# LCD.net
KiCad netlist of a schematic drawn in Altium Designer
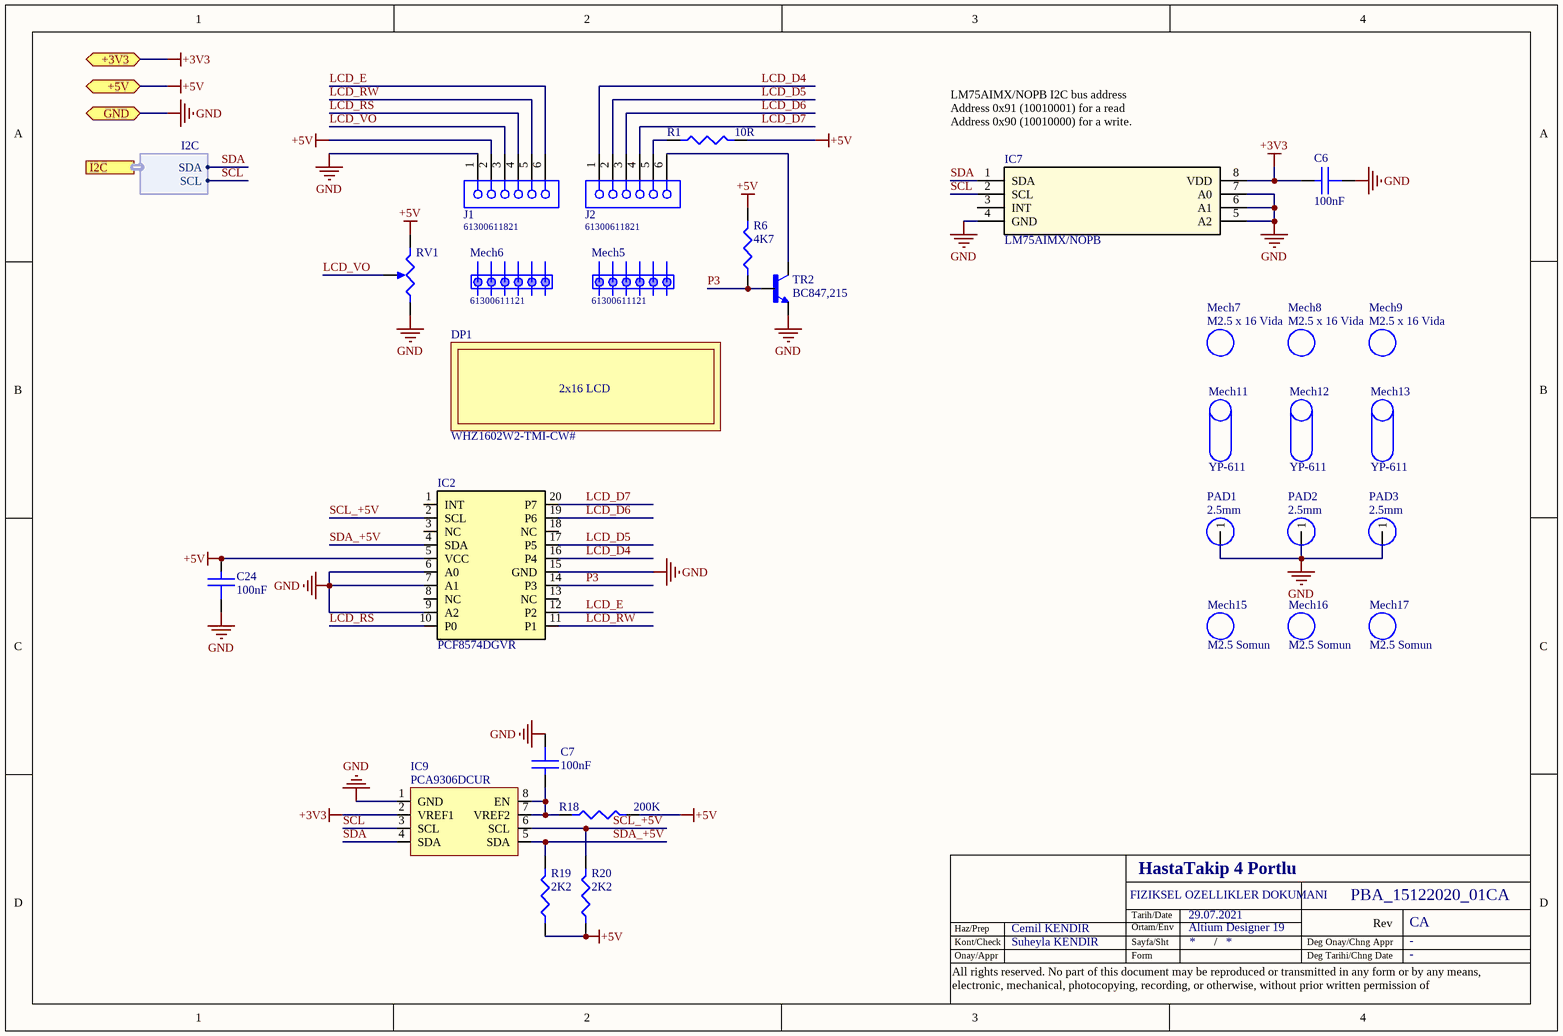
[diagram p0: LCD.SchDoc]

(export (version "E")
  (design (tool "Eeschema 10.0.6"))
  (components
    (comp (ref "C6")
      (value "100nF")
      (footprint "C0603")
      (description "100nF, 25V, X7R, 10%, 0603")
      (fields
        (field (name "MANUFACTURER") "Yageo")
        (field (name "MANUFACTURER PART NUMBER") "CC0603KRX7R8BB104")
      )
      (libsource (lib "McmLibrary") (part "CC0603KRX7R8BB104"))
    )
    (comp (ref "C7")
      (value "100nF")
      (footprint "C0603")
      (description "100nF, 25V, X7R, 10%, 0603")
      (fields
        (field (name "MANUFACTURER") "Yageo")
        (field (name "MANUFACTURER PART NUMBER") "CC0603KRX7R8BB104")
      )
      (libsource (lib "McmLibrary") (part "CC0603KRX7R8BB104"))
    )
    (comp (ref "C24")
      (value "100nF")
      (footprint "C0603")
      (description "100nF, 25V, X7R, 10%, 0603")
      (fields
        (field (name "MANUFACTURER") "Yageo")
        (field (name "MANUFACTURER PART NUMBER") "CC0603KRX7R8BB104")
      )
      (libsource (lib "McmLibrary") (part "CC0603KRX7R8BB104"))
    )
    (comp (ref "DP1")
      (value "WHZ1602W2-TMI-CW#")
      (footprint "WHZ1602W2-TMI-CW#")
      (description "LCD MOD 16*2 80X36X10MM LEDB.LIGHT WHITE")
      (fields (field (name "MANUFACTURER") "Winstar"))
      (libsource (lib "McmLibrary") (part "WHZ1602W2-TMI-CW#"))
    )
    (comp (ref "IC2")
      (value "PCF8574DGVR")
      (footprint "DGV20")
      (description "8-bit 2.5- to 5.5-V I2C/SMBus I/O expander with interrupt 20-TVSOP -40 to 85")
      (fields (field (name "MANUFACTURER") "Texas Instruments"))
      (libsource (lib "McmLibrary") (part "PCF8574DGVR"))
    )
    (comp (ref "IC7")
      (value "LM75AIMX/NOPB")
      (footprint "SO08")
      (description "SENSOR DIGITAL -55C-125C 8SOIC")
      (fields (field (name "MANUFACTURER") "TI National Semiconductor"))
      (libsource (lib "Sensors") (part "LM75AIMX/NOPB"))
    )
    (comp (ref "IC9")
      (value "PCA9306DCUR")
      (footprint "SOP50P310X90-8N")
      (description "TEXAS INSTRUMENTS - PCA9306DCUR - 2 BIT VOLTAGE LEVEL TRANSLATOR VSSOP8")
      (fields (field (name "MANUFACTURER") "Texas Instruments"))
      (libsource (lib "McmLibrary") (part "PCA9306DCUR"))
    )
    (comp (ref "J1")
      (value "61300611821")
      (footprint "61300611821")
      (description "WR-PHD Socket Header, THT, pitch 2.54mm, Single Row, Vertical, 6pin")
      (fields (field (name "PUBLISHER") "Wurth Elektronik"))
      (libsource (lib "McmLibrary") (part "61300611821"))
    )
    (comp (ref "J2")
      (value "61300611821")
      (footprint "61300611821")
      (description "WR-PHD Socket Header, THT, pitch 2.54mm, Single Row, Vertical, 6pin")
      (fields (field (name "PUBLISHER") "Wurth Elektronik"))
      (libsource (lib "McmLibrary") (part "61300611821"))
    )
    (comp (ref "Mech5")
      (value "61300611121")
      (footprint "61300611121")
      (description "WR-PHD Pin Header, THT, pitch 2.54mm, Single Row, Vertical, 6pin")
      (fields (field (name "PUBLISHER") "Wurth Elektronik"))
      (libsource (lib "McmLibrary") (part "61300611121"))
    )
    (comp (ref "Mech6")
      (value "61300611121")
      (footprint "61300611121")
      (description "WR-PHD Pin Header, THT, pitch 2.54mm, Single Row, Vertical, 6pin")
      (fields (field (name "PUBLISHER") "Wurth Elektronik"))
      (libsource (lib "McmLibrary") (part "61300611121"))
    )
    (comp (ref "Mech7")
      (value "M2.5 x 16 Vida")
      (footprint "M2.5 x 16")
      (description "M2.5 x 16 YSB Vida")
      (libsource (lib "McmLibrary") (part "M2.5 x 16 Vida"))
    )
    (comp (ref "Mech8")
      (value "M2.5 x 16 Vida")
      (footprint "M2.5 x 16")
      (description "M2.5 x 16 YSB Vida")
      (libsource (lib "McmLibrary") (part "M2.5 x 16 Vida"))
    )
    (comp (ref "Mech9")
      (value "M2.5 x 16 Vida")
      (footprint "M2.5 x 16")
      (description "M2.5 x 16 YSB Vida")
      (libsource (lib "McmLibrary") (part "M2.5 x 16 Vida"))
    )
    (comp (ref "Mech11")
      (value "YP-611")
      (footprint "YP-611 - 11 mm")
      (description "Distance 2.5mmx11mm")
      (libsource (lib "McmLibrary") (part "YP-611"))
    )
    (comp (ref "Mech12")
      (value "YP-611")
      (footprint "YP-611 - 11 mm")
      (description "Distance 2.5mmx11mm")
      (libsource (lib "McmLibrary") (part "YP-611"))
    )
    (comp (ref "Mech13")
      (value "YP-611")
      (footprint "YP-611 - 11 mm")
      (description "Distance 2.5mmx11mm")
      (libsource (lib "McmLibrary") (part "YP-611"))
    )
    (comp (ref "Mech15")
      (value "M2.5 Somun")
      (footprint "M2.5")
      (libsource (lib "McmLibrary") (part "M2.5 Somun"))
    )
    (comp (ref "Mech16")
      (value "M2.5 Somun")
      (footprint "M2.5")
      (libsource (lib "McmLibrary") (part "M2.5 Somun"))
    )
    (comp (ref "Mech17")
      (value "M2.5 Somun")
      (footprint "M2.5")
      (libsource (lib "McmLibrary") (part "M2.5 Somun"))
    )
    (comp (ref "PAD1")
      (value "2.5mm")
      (footprint "2.5mm x 5mm")
      (description "5mm x 2.5mm Pad")
      (libsource (lib "McmLibrary") (part "2.5mm x 5mm PAD"))
    )
    (comp (ref "PAD2")
      (value "2.5mm")
      (footprint "2.5mm x 5mm")
      (description "5mm x 2.5mm Pad")
      (libsource (lib "McmLibrary") (part "2.5mm x 5mm PAD"))
    )
    (comp (ref "PAD3")
      (value "2.5mm")
      (footprint "2.5mm x 5mm")
      (description "5mm x 2.5mm Pad")
      (libsource (lib "McmLibrary") (part "2.5mm x 5mm PAD"))
    )
    (comp (ref "R1")
      (value "10R")
      (footprint "R0603")
      (description "10R ,%1 ,1/10 W ,0603")
      (fields
        (field (name "MANUFACTURER") "Yageo")
        (field (name "MANUFACTURER PART NUMBER") "RC0603FR-0710RL")
      )
      (libsource (lib "McmLibrary") (part "RC0603FR-0710RL"))
    )
    (comp (ref "R6")
      (value "4K7")
      (footprint "R0603")
      (description "4K7 ,%1 ,1/10 W ,0603")
      (fields
        (field (name "MANUFACTURER") "Yageo")
        (field (name "MANUFACTURER PART NUMBER") "RC0603FR-074K7L")
      )
      (libsource (lib "McmLibrary") (part "RC0603FR-074K7L"))
    )
    (comp (ref "R18")
      (value "200K")
      (footprint "R0603")
      (description "200K, %1, 1/10W, 0603")
      (fields
        (field (name "MANUFACTURER") "Yageo")
        (field (name "MANUFACTURER PART NUMBER") "RC0603FR-07200KL")
      )
      (libsource (lib "McmLibrary") (part "RC0603FR-07200KL"))
    )
    (comp (ref "R19")
      (value "2K2")
      (footprint "R0603")
      (description "2K2, 1%, 0.1W, 0603")
      (fields
        (field (name "MANUFACTURER") "Yageo")
        (field (name "MANUFACTURER PART NUMBER") "RC0603FR-072K2L")
      )
      (libsource (lib "McmLibrary") (part "RC0603FR-072K2L"))
    )
    (comp (ref "R20")
      (value "2K2")
      (footprint "R0603")
      (description "2K2, 1%, 0.1W, 0603")
      (fields
        (field (name "MANUFACTURER") "Yageo")
        (field (name "MANUFACTURER PART NUMBER") "RC0603FR-072K2L")
      )
      (libsource (lib "McmLibrary") (part "RC0603FR-072K2L"))
    )
    (comp (ref "RV1")
      (value "L-KLS4-WH06-2A-103")
      (footprint "L-KLS4-WH06-2A-103")
      (description "10k TRIMPOT")
      (fields (field (name "MANUFACTURER") "KLS ELECTRONIC"))
      (libsource (lib "McmLibrary") (part "L-KLS4-WH06-2A-103"))
    )
    (comp (ref "TR2")
      (value "BC847,215")
      (footprint "SOT23")
      (description "TRANS NPN 45V 0.1A SOT23")
      (fields (field (name "MANUFACTURER") "Nexperia"))
      (libsource (lib "McmLibrary") (part "BC847,215"))
    )
  )
  (nets
    (net (code "2") (name "+3V3") (class "Default")
      (node (ref "C6") (pin "1") (pintype "passive"))
      (node (ref "IC7") (pin "8") (pinfunction "VDD_8") (pintype "passive"))
      (node (ref "IC9") (pin "2") (pinfunction "VREF1_2") (pintype "passive"))
    )
    (net (code "3") (name "+5V") (class "Default")
      (node (ref "C24") (pin "1") (pintype "passive"))
      (node (ref "IC2") (pin "5") (pinfunction "VCC_5") (pintype "passive"))
      (node (ref "J1") (pin "2") (pinfunction "2_2") (pintype "passive"))
      (node (ref "R1") (pin "2") (pinfunction "2_2") (pintype "passive"))
      (node (ref "R18") (pin "2") (pinfunction "2_2") (pintype "passive"))
      (node (ref "R19") (pin "1") (pinfunction "1_1") (pintype "passive"))
      (node (ref "R20") (pin "1") (pinfunction "1_1") (pintype "passive"))
      (node (ref "R6") (pin "2") (pinfunction "2_2") (pintype "passive"))
      (node (ref "RV1") (pin "2") (pinfunction "2_2") (pintype "passive"))
    )
    (net (code "4") (name "/LCD_D4") (class "Default")
      (node (ref "IC2") (pin "16") (pinfunction "P4_16") (pintype "passive"))
      (node (ref "J2") (pin "1") (pinfunction "1_1") (pintype "passive"))
    )
    (net (code "5") (name "/LCD_D5") (class "Default")
      (node (ref "IC2") (pin "17") (pinfunction "P5_17") (pintype "passive"))
      (node (ref "J2") (pin "2") (pinfunction "2_2") (pintype "passive"))
    )
    (net (code "6") (name "/LCD_D6") (class "Default")
      (node (ref "IC2") (pin "19") (pinfunction "P6_19") (pintype "passive"))
      (node (ref "J2") (pin "3") (pinfunction "3_3") (pintype "passive"))
    )
    (net (code "7") (name "/LCD_D7") (class "Default")
      (node (ref "IC2") (pin "20") (pinfunction "P7_20") (pintype "passive"))
      (node (ref "J2") (pin "4") (pinfunction "4_4") (pintype "passive"))
    )
    (net (code "8") (name "/LCD_E") (class "Default")
      (node (ref "IC2") (pin "12") (pinfunction "P2_12") (pintype "passive"))
      (node (ref "J1") (pin "6") (pinfunction "6_6") (pintype "passive"))
    )
    (net (code "9") (name "/LCD_RS") (class "Default")
      (node (ref "IC2") (pin "10") (pinfunction "P0_10") (pintype "passive"))
      (node (ref "J1") (pin "4") (pinfunction "4_4") (pintype "passive"))
    )
    (net (code "10") (name "/LCD_RW") (class "Default")
      (node (ref "IC2") (pin "11") (pinfunction "P1_11") (pintype "passive"))
      (node (ref "J1") (pin "5") (pinfunction "5_5") (pintype "passive"))
    )
    (net (code "11") (name "/LCD_VO") (class "Default")
      (node (ref "J1") (pin "3") (pinfunction "3_3") (pintype "passive"))
      (node (ref "RV1") (pin "3") (pinfunction "3_3") (pintype "passive"))
    )
    (net (code "12") (name "/P3") (class "Default")
      (node (ref "IC2") (pin "14") (pinfunction "P3_14") (pintype "passive"))
      (node (ref "R6") (pin "1") (pinfunction "1_1") (pintype "passive"))
      (node (ref "TR2") (pin "1") (pinfunction "B_1") (pintype "passive"))
    )
    (net (code "13") (name "/SCL") (class "Default")
      (node (ref "IC7") (pin "2") (pinfunction "SCL_2") (pintype "passive"))
      (node (ref "IC9") (pin "3") (pinfunction "SCL_3") (pintype "passive"))
    )
    (net (code "14") (name "/SCL_+5V") (class "Default")
      (node (ref "IC2") (pin "2") (pinfunction "SCL_2") (pintype "passive"))
      (node (ref "IC9") (pin "6") (pinfunction "SCL_6") (pintype "passive"))
      (node (ref "R20") (pin "2") (pinfunction "2_2") (pintype "passive"))
    )
    (net (code "15") (name "/SDA") (class "Default")
      (node (ref "IC7") (pin "1") (pinfunction "SDA_1") (pintype "passive"))
      (node (ref "IC9") (pin "4") (pinfunction "SDA_4") (pintype "passive"))
    )
    (net (code "16") (name "/SDA_+5V") (class "Default")
      (node (ref "IC2") (pin "4") (pinfunction "SDA_4") (pintype "passive"))
      (node (ref "IC9") (pin "5") (pinfunction "SDA_5") (pintype "passive"))
      (node (ref "R19") (pin "2") (pinfunction "2_2") (pintype "passive"))
    )
    (net (code "18") (name "GND") (class "Default")
      (node (ref "C24") (pin "2") (pintype "passive"))
      (node (ref "C6") (pin "2") (pintype "passive"))
      (node (ref "C7") (pin "2") (pintype "passive"))
      (node (ref "IC2") (pin "15") (pinfunction "GND_15") (pintype "passive"))
      (node (ref "IC2") (pin "6") (pinfunction "A0_6") (pintype "passive"))
      (node (ref "IC2") (pin "7") (pinfunction "A1_7") (pintype "passive"))
      (node (ref "IC2") (pin "9") (pinfunction "A2_9") (pintype "passive"))
      (node (ref "IC7") (pin "4") (pinfunction "GND_4") (pintype "passive"))
      (node (ref "IC7") (pin "5") (pinfunction "A2_5") (pintype "passive"))
      (node (ref "IC7") (pin "6") (pinfunction "A1_6") (pintype "passive"))
      (node (ref "IC7") (pin "7") (pinfunction "A0_7") (pintype "passive"))
      (node (ref "IC9") (pin "1") (pinfunction "GND_1") (pintype "passive"))
      (node (ref "J1") (pin "1") (pinfunction "1_1") (pintype "passive"))
      (node (ref "PAD1") (pin "1") (pinfunction "1_1") (pintype "passive"))
      (node (ref "PAD2") (pin "1") (pinfunction "1_1") (pintype "passive"))
      (node (ref "PAD3") (pin "1") (pinfunction "1_1") (pintype "passive"))
      (node (ref "RV1") (pin "1") (pinfunction "1_1") (pintype "passive"))
      (node (ref "TR2") (pin "2") (pinfunction "E_2") (pintype "passive"))
    )
    (net (code "19") (name "Net-(IC9-EN)") (class "Default")
      (node (ref "C7") (pin "1") (pintype "passive"))
      (node (ref "IC9") (pin "7") (pinfunction "VREF2_7") (pintype "passive"))
      (node (ref "IC9") (pin "8") (pinfunction "EN_8") (pintype "passive"))
      (node (ref "R18") (pin "1") (pinfunction "1_1") (pintype "passive"))
    )
    (net (code "20") (name "Net-(J2-Pad5)") (class "Default")
      (node (ref "J2") (pin "5") (pinfunction "5_5") (pintype "passive"))
      (node (ref "R1") (pin "1") (pinfunction "1_1") (pintype "passive"))
    )
    (net (code "21") (name "Net-(TR2-C)") (class "Default")
      (node (ref "J2") (pin "6") (pinfunction "6_6") (pintype "passive"))
      (node (ref "TR2") (pin "3") (pinfunction "C_3") (pintype "passive"))
    )
    (net (code "22") (name "unconnected-(IC2-INT-Pad1)") (class "Default")
      (node (ref "IC2") (pin "1") (pinfunction "INT_1") (pintype "passive"))
    )
    (net (code "23") (name "unconnected-(IC2-NC-Pad3)") (class "Default")
      (node (ref "IC2") (pin "3") (pinfunction "NC_3") (pintype "passive"))
    )
    (net (code "24") (name "unconnected-(IC2-NC-Pad8)") (class "Default")
      (node (ref "IC2") (pin "8") (pinfunction "NC_8") (pintype "passive"))
    )
    (net (code "25") (name "unconnected-(IC2-NC-Pad13)") (class "Default")
      (node (ref "IC2") (pin "13") (pinfunction "NC_13") (pintype "passive"))
    )
    (net (code "26") (name "unconnected-(IC2-NC-Pad18)") (class "Default")
      (node (ref "IC2") (pin "18") (pinfunction "NC_18") (pintype "passive"))
    )
    (net (code "27") (name "unconnected-(IC7-INT-Pad3)") (class "Default")
      (node (ref "IC7") (pin "3") (pinfunction "INT_3") (pintype "passive"))
    )
  )
)
